# dummy_load_schematic.net
KiCad netlist of a schematic drawn in EAGLE
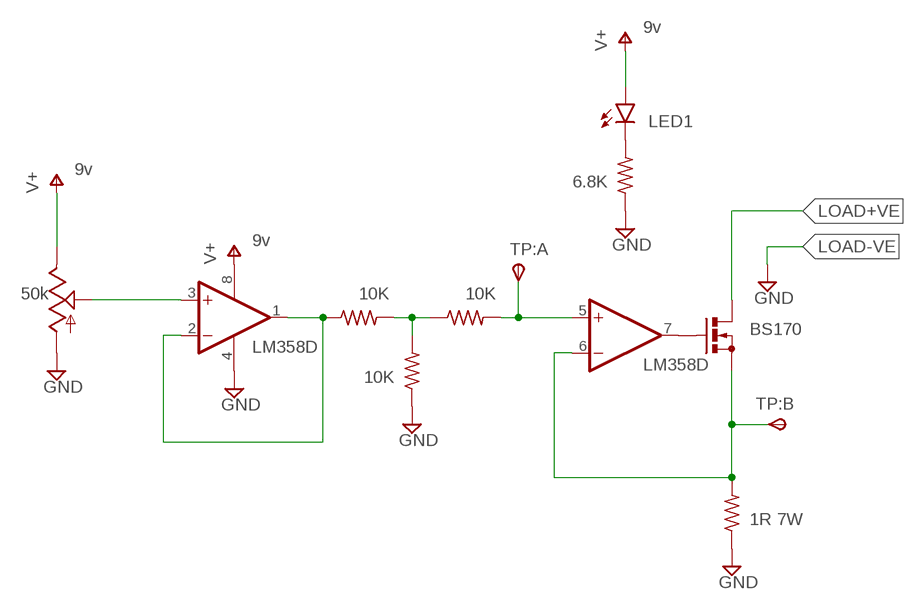
[diagram p0: schematic, sheet 1]

(export (version "E")
  (design (tool "Eeschema 10.0.6"))
  (components
    (comp (ref "IC1")
      (value "LM358D")
      (footprint "eagle-import:SO08")
      (libsource (lib "eagle-import") (part "LM358D"))
    )
    (comp (ref "IC2")
      (value "OP1277RM")
      (footprint "eagle-import:MSOP08")
      (libsource (lib "eagle-import") (part "OP1277RM"))
    )
    (comp (ref "LED1")
      (value "LED5MM")
      (footprint "eagle-import:LED5MM")
      (libsource (lib "eagle-import") (part "LED5MM"))
    )
    (comp (ref "Q1")
      (value "BS170")
      (footprint "eagle-import:SOT54E")
      (libsource (lib "eagle-import") (part "BS170"))
    )
    (comp (ref "R1")
      (value "US-EVUF3J")
      (footprint "eagle-import:EVUFXJ")
      (fields (field (name "LABEL") "50k"))
      (libsource (lib "eagle-import") (part "US-EVUF3J"))
    )
    (comp (ref "R2")
      (value "R-US_WSC0001")
      (footprint "eagle-import:WSC0001")
      (fields (field (name "LABEL") "10K"))
      (libsource (lib "eagle-import") (part "R-US_WSC0001"))
    )
    (comp (ref "R3")
      (value "R-US_WSC0001")
      (footprint "eagle-import:WSC0001")
      (fields (field (name "LABEL") "1R 7W"))
      (libsource (lib "eagle-import") (part "R-US_WSC0001"))
    )
    (comp (ref "R5")
      (value "R-US_WSC0001")
      (footprint "eagle-import:WSC0001")
      (fields (field (name "LABEL") "10K"))
      (libsource (lib "eagle-import") (part "R-US_WSC0001"))
    )
    (comp (ref "R6")
      (value "R-US_WSC0001")
      (footprint "eagle-import:WSC0001")
      (fields (field (name "LABEL") "10K"))
      (libsource (lib "eagle-import") (part "R-US_WSC0001"))
    )
    (comp (ref "R7")
      (value "R-US_WSC0001")
      (footprint "eagle-import:WSC0001")
      (fields (field (name "LABEL") "6.8K"))
      (libsource (lib "eagle-import") (part "R-US_WSC0001"))
    )
    (comp (ref "TP1")
      (value "TPSPAD1-20Y")
      (footprint "eagle-import:P1-20Y")
      (fields (field (name "TP_SIGNAL_NAME") "TP:A"))
      (libsource (lib "eagle-import") (part "TPSPAD1-20Y"))
    )
    (comp (ref "TP2")
      (value "TPSPAD1-20Y")
      (footprint "eagle-import:P1-20Y")
      (fields (field (name "TP_SIGNAL_NAME") "TP:B"))
      (libsource (lib "eagle-import") (part "TPSPAD1-20Y"))
    )
  )
  (nets
    (net (code "1") (name "LOAD+VE") (class "Default")
      (node (ref "Q1") (pin "D") (pinfunction "D_D") (pintype "passive"))
    )
    (net (code "2") (name "LOAD-VE") (class "Default")
      (node (ref "IC2") (pin "4") (pinfunction "V-_4") (pintype "power_in"))
      (node (ref "R1") (pin "1") (pinfunction "A_1") (pintype "passive"))
      (node (ref "R3") (pin "1") (pinfunction "1_1") (pintype "passive"))
      (node (ref "R6") (pin "1") (pinfunction "1_1") (pintype "passive"))
      (node (ref "R7") (pin "1") (pinfunction "1_1") (pintype "passive"))
    )
    (net (code "3") (name "Net-(IC1A-+IN)") (class "Default")
      (node (ref "IC1") (pin "3") (pinfunction "+IN_3") (pintype "input"))
      (node (ref "R1") (pin "2") (pinfunction "S_2") (pintype "passive"))
    )
    (net (code "4") (name "Net-(IC1A--IN)") (class "Default")
      (node (ref "IC1") (pin "1") (pinfunction "OUT_1") (pintype "output"))
      (node (ref "IC1") (pin "2") (pinfunction "-IN_2") (pintype "input"))
      (node (ref "R2") (pin "1") (pinfunction "1_1") (pintype "passive"))
    )
    (net (code "5") (name "Net-(IC1B-+IN)") (class "Default")
      (node (ref "IC1") (pin "5") (pinfunction "+IN_5") (pintype "input"))
      (node (ref "R5") (pin "2") (pinfunction "2_2") (pintype "passive"))
      (node (ref "TP1") (pin "TP") (pinfunction "PP_TP") (pintype "input"))
    )
    (net (code "6") (name "Net-(IC1B--IN)") (class "Default")
      (node (ref "IC1") (pin "6") (pinfunction "-IN_6") (pintype "input"))
      (node (ref "Q1") (pin "S") (pinfunction "S_S") (pintype "passive"))
      (node (ref "R3") (pin "2") (pinfunction "2_2") (pintype "passive"))
      (node (ref "TP2") (pin "TP") (pinfunction "PP_TP") (pintype "input"))
    )
    (net (code "7") (name "Net-(IC1B-OUT)") (class "Default")
      (node (ref "IC1") (pin "7") (pinfunction "OUT_7") (pintype "output"))
      (node (ref "Q1") (pin "G") (pinfunction "G_G") (pintype "passive"))
    )
    (net (code "8") (name "Net-(LED1-C)") (class "Default")
      (node (ref "LED1") (pin "K") (pinfunction "C_K") (pintype "passive"))
      (node (ref "R7") (pin "2") (pinfunction "2_2") (pintype "passive"))
    )
    (net (code "9") (name "Net-(R2-Pad2)") (class "Default")
      (node (ref "R2") (pin "2") (pinfunction "2_2") (pintype "passive"))
      (node (ref "R5") (pin "1") (pinfunction "1_1") (pintype "passive"))
      (node (ref "R6") (pin "2") (pinfunction "2_2") (pintype "passive"))
    )
    (net (code "10") (name "V+") (class "Default")
      (node (ref "IC2") (pin "8") (pinfunction "V+_8") (pintype "power_in"))
      (node (ref "LED1") (pin "A") (pinfunction "A_A") (pintype "passive"))
      (node (ref "R1") (pin "3") (pinfunction "E_3") (pintype "passive"))
    )
  )
)
